# DAU_Kupplung_3phasig_V1_13.net
KiCad netlist of a schematic drawn in EAGLE
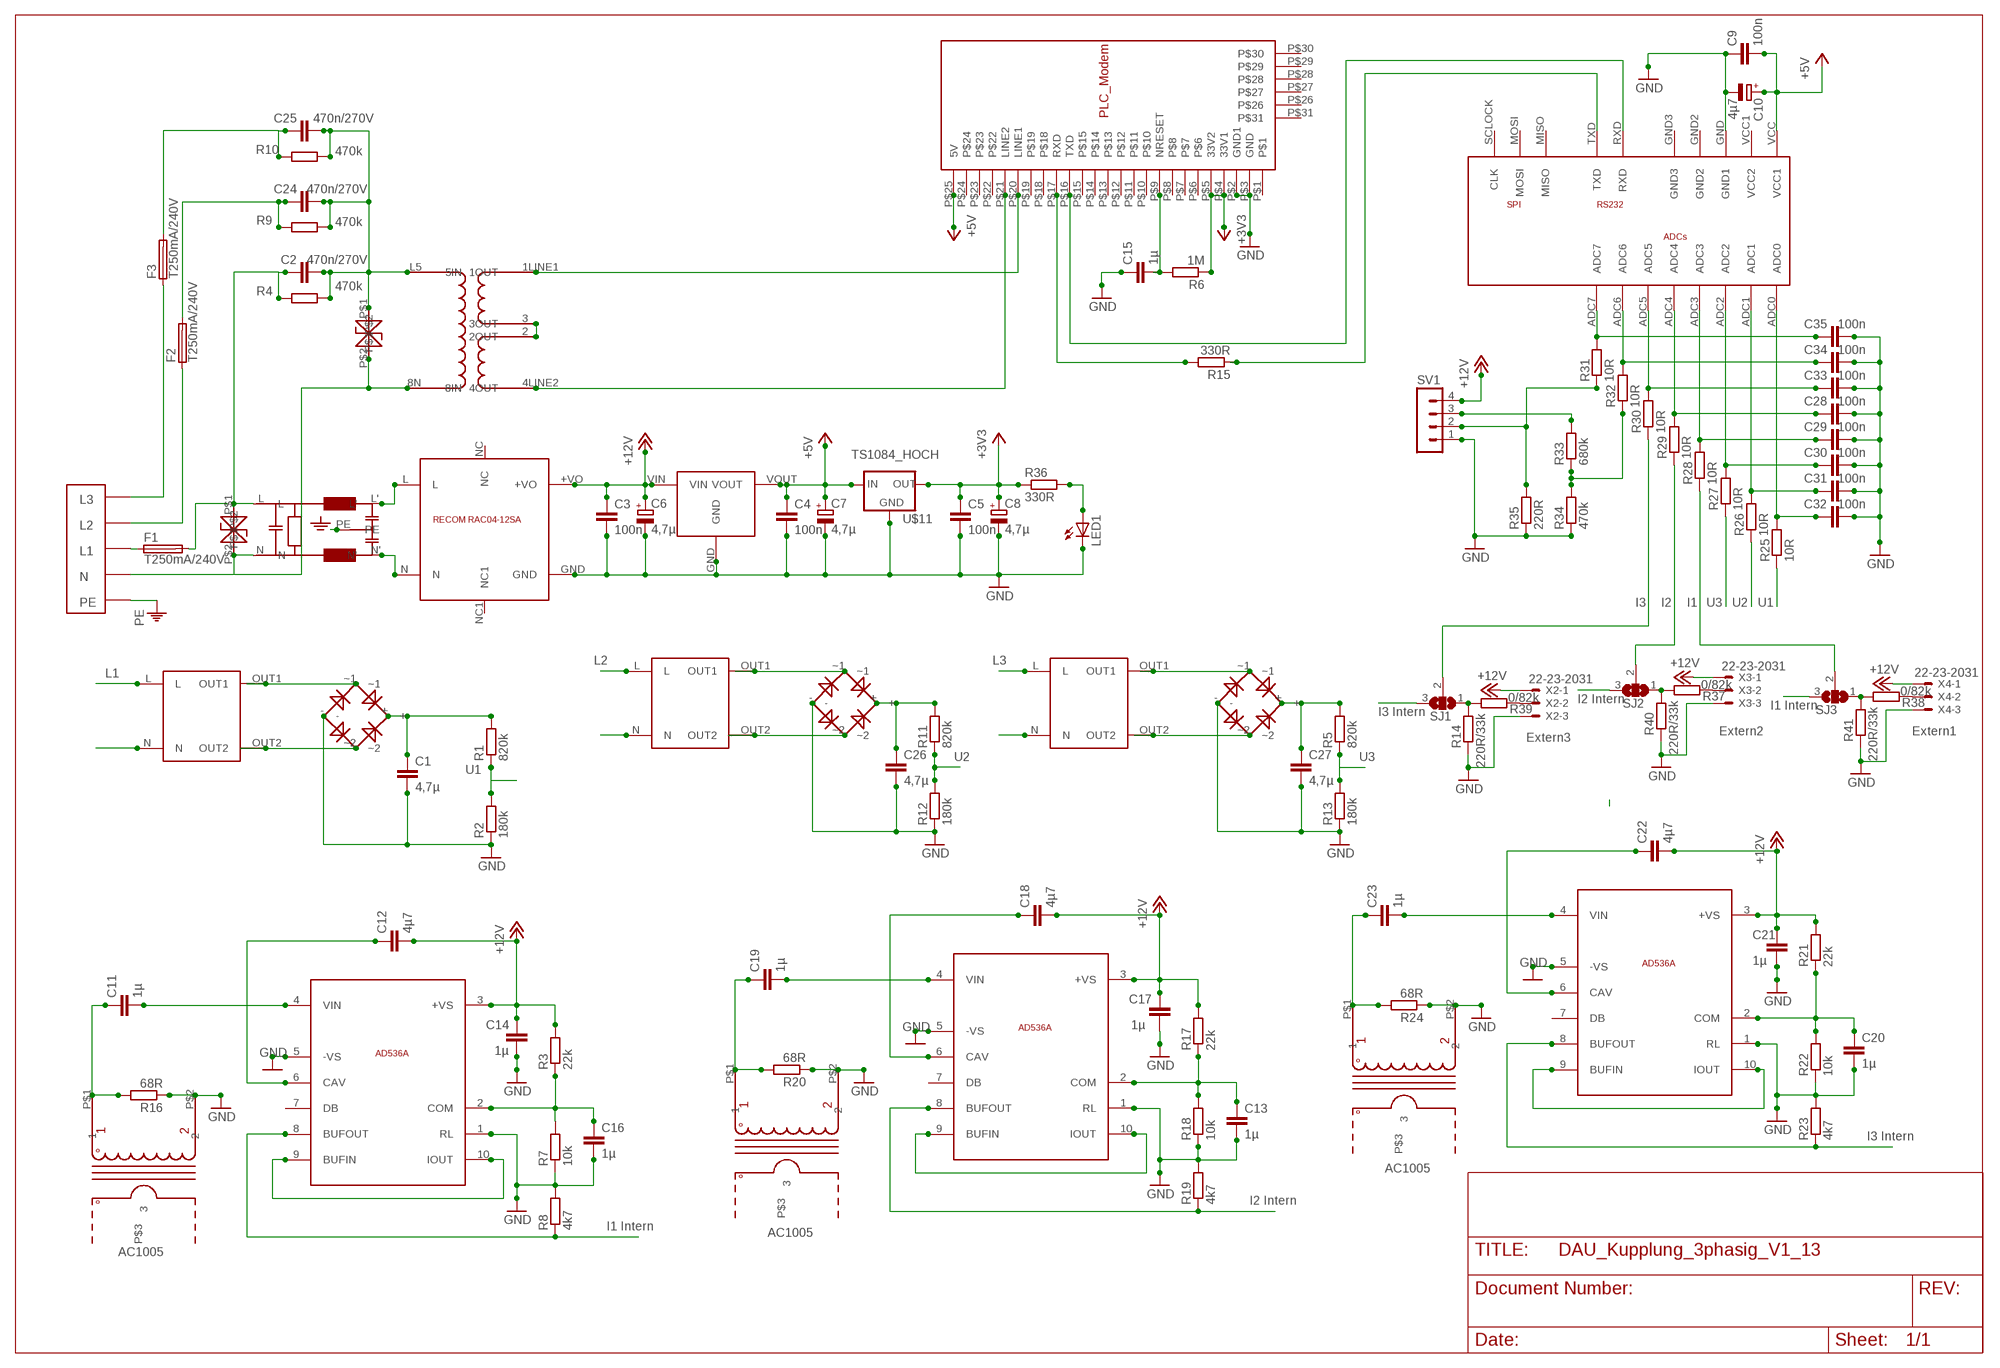
[diagram p0: schematic, sheet 1]

(export (version "E")
  (design (tool "Eeschema 10.0.6"))
  (components
    (comp (ref "AC1002_1")
      (value "AC1010")
      (footprint "eagle-import:AC1010")
      (libsource (lib "eagle-import") (part "AC1010"))
    )
    (comp (ref "C1")
      (value "4,7µ")
      (footprint "eagle-import:C1206")
      (libsource (lib "eagle-import") (part "C-EUC1206"))
    )
    (comp (ref "C2")
      (value "470n/270V")
      (footprint "eagle-import:C225-087X268")
      (libsource (lib "eagle-import") (part "C-EU225-087X268"))
    )
    (comp (ref "C3")
      (value "100n")
      (footprint "eagle-import:C0805K")
      (libsource (lib "eagle-import") (part "C-EUC0805K"))
    )
    (comp (ref "C4")
      (value "100n")
      (footprint "eagle-import:C0805K")
      (libsource (lib "eagle-import") (part "C-EUC0805K"))
    )
    (comp (ref "C5")
      (value "100n")
      (footprint "eagle-import:C0805K")
      (libsource (lib "eagle-import") (part "C-EUC0805K"))
    )
    (comp (ref "C6")
      (value "4,7µ")
      (footprint "eagle-import:E2,5-6")
      (libsource (lib "eagle-import") (part "resistor_CPOL-EUE2.5-6"))
    )
    (comp (ref "C7")
      (value "4,7µ")
      (footprint "eagle-import:E2,5-6")
      (libsource (lib "eagle-import") (part "resistor_CPOL-EUE2.5-6"))
    )
    (comp (ref "C8")
      (value "4,7µ")
      (footprint "eagle-import:E2,5-6")
      (libsource (lib "eagle-import") (part "resistor_CPOL-EUE2.5-6"))
    )
    (comp (ref "C9")
      (value "100n")
      (footprint "eagle-import:C0805K")
      (libsource (lib "eagle-import") (part "C-EUC0805K"))
    )
    (comp (ref "C10")
      (value "4µ7")
      (footprint "eagle-import:E2,5-6E")
      (libsource (lib "eagle-import") (part "CPOL-EUE2,5-6E"))
    )
    (comp (ref "C11")
      (value "1µ")
      (footprint "eagle-import:C0805K")
      (libsource (lib "eagle-import") (part "C-EUC0805K"))
    )
    (comp (ref "C12")
      (value "4µ7")
      (footprint "eagle-import:C0805K")
      (libsource (lib "eagle-import") (part "C-EUC0805K"))
    )
    (comp (ref "C13")
      (value "1µ")
      (footprint "eagle-import:C0805K")
      (libsource (lib "eagle-import") (part "C-EUC0805K"))
    )
    (comp (ref "C14")
      (value "1µ")
      (footprint "eagle-import:C0805K")
      (libsource (lib "eagle-import") (part "C-EUC0805K"))
    )
    (comp (ref "C15")
      (value "1µ")
      (footprint "eagle-import:C0805K")
      (libsource (lib "eagle-import") (part "C-EUC0805K"))
    )
    (comp (ref "C16")
      (value "1µ")
      (footprint "eagle-import:C0805K")
      (libsource (lib "eagle-import") (part "C-EUC0805K"))
    )
    (comp (ref "C17")
      (value "1µ")
      (footprint "eagle-import:C0805K")
      (libsource (lib "eagle-import") (part "C-EUC0805K"))
    )
    (comp (ref "C18")
      (value "4µ7")
      (footprint "eagle-import:C0805K")
      (libsource (lib "eagle-import") (part "C-EUC0805K"))
    )
    (comp (ref "C19")
      (value "1µ")
      (footprint "eagle-import:C0805K")
      (libsource (lib "eagle-import") (part "C-EUC0805K"))
    )
    (comp (ref "C20")
      (value "1µ")
      (footprint "eagle-import:C0805K")
      (libsource (lib "eagle-import") (part "C-EUC0805K"))
    )
    (comp (ref "C21")
      (value "1µ")
      (footprint "eagle-import:C0805K")
      (libsource (lib "eagle-import") (part "C-EUC0805K"))
    )
    (comp (ref "C22")
      (value "4µ7")
      (footprint "eagle-import:C0805K")
      (libsource (lib "eagle-import") (part "C-EUC0805K"))
    )
    (comp (ref "C23")
      (value "1µ")
      (footprint "eagle-import:C0805K")
      (libsource (lib "eagle-import") (part "C-EUC0805K"))
    )
    (comp (ref "C24")
      (value "470n/270V")
      (footprint "eagle-import:C225-087X268")
      (libsource (lib "eagle-import") (part "C-EU225-087X268"))
    )
    (comp (ref "C25")
      (value "470n/270V")
      (footprint "eagle-import:C225-087X268")
      (libsource (lib "eagle-import") (part "C-EU225-087X268"))
    )
    (comp (ref "C26")
      (value "4,7µ")
      (footprint "eagle-import:C1206")
      (libsource (lib "eagle-import") (part "C-EUC1206"))
    )
    (comp (ref "C27")
      (value "4,7µ")
      (footprint "eagle-import:C1206")
      (libsource (lib "eagle-import") (part "C-EUC1206"))
    )
    (comp (ref "C28")
      (value "100n")
      (footprint "eagle-import:C0805K")
      (libsource (lib "eagle-import") (part "C-EUC0805K"))
    )
    (comp (ref "C29")
      (value "100n")
      (footprint "eagle-import:C0805K")
      (libsource (lib "eagle-import") (part "C-EUC0805K"))
    )
    (comp (ref "C30")
      (value "100n")
      (footprint "eagle-import:C0805K")
      (libsource (lib "eagle-import") (part "C-EUC0805K"))
    )
    (comp (ref "C31")
      (value "100n")
      (footprint "eagle-import:C0805K")
      (libsource (lib "eagle-import") (part "C-EUC0805K"))
    )
    (comp (ref "C32")
      (value "100n")
      (footprint "eagle-import:C0805K")
      (libsource (lib "eagle-import") (part "C-EUC0805K"))
    )
    (comp (ref "C33")
      (value "100n")
      (footprint "eagle-import:C0805K")
      (libsource (lib "eagle-import") (part "C-EUC0805K"))
    )
    (comp (ref "C34")
      (value "100n")
      (footprint "eagle-import:C0805K")
      (libsource (lib "eagle-import") (part "C-EUC0805K"))
    )
    (comp (ref "C35")
      (value "100n")
      (footprint "eagle-import:C0805K")
      (libsource (lib "eagle-import") (part "C-EUC0805K"))
    )
    (comp (ref "F1")
      (value "T250mA/240V")
      (footprint "eagle-import:TR5")
      (libsource (lib "eagle-import") (part "TR5"))
    )
    (comp (ref "F2")
      (value "T250mA/240V")
      (footprint "eagle-import:TR5")
      (fields (field (name "OC_FARNELL") "unknown") (field (name "OC_NEWARK") "unknown"))
      (libsource (lib "eagle-import") (part "TR5"))
    )
    (comp (ref "F3")
      (value "T250mA/240V")
      (footprint "eagle-import:TR5")
      (fields (field (name "OC_FARNELL") "unknown") (field (name "OC_NEWARK") "unknown"))
      (libsource (lib "eagle-import") (part "TR5"))
    )
    (comp (ref "LED1")
      (value "LEDSQR2X5")
      (footprint "eagle-import:LED2X5")
      (libsource (lib "eagle-import") (part "LEDSQR2X5"))
    )
    (comp (ref "P6KE300CA")
      (value "P6KE300CA")
      (footprint "eagle-import:TSV")
      (libsource (lib "eagle-import") (part "TSV"))
    )
    (comp (ref "R1")
      (value "820k")
      (footprint "eagle-import:R0805")
      (libsource (lib "eagle-import") (part "R-EU_R0805"))
    )
    (comp (ref "R2")
      (value "180k")
      (footprint "eagle-import:R0805")
      (libsource (lib "eagle-import") (part "R-EU_R0805"))
    )
    (comp (ref "R3")
      (value "22k")
      (footprint "eagle-import:R0805")
      (libsource (lib "eagle-import") (part "R-EU_R0805"))
    )
    (comp (ref "R4")
      (value "470k")
      (footprint "eagle-import:0204_7")
      (libsource (lib "eagle-import") (part "R-EU_0204/7"))
    )
    (comp (ref "R5")
      (value "820k")
      (footprint "eagle-import:R0805")
      (libsource (lib "eagle-import") (part "R-EU_R0805"))
    )
    (comp (ref "R6")
      (value "1M")
      (footprint "eagle-import:R0805")
      (libsource (lib "eagle-import") (part "R-EU_R0805"))
    )
    (comp (ref "R7")
      (value "10k")
      (footprint "eagle-import:R0805")
      (libsource (lib "eagle-import") (part "R-EU_R0805"))
    )
    (comp (ref "R8")
      (value "4k7")
      (footprint "eagle-import:R0805")
      (libsource (lib "eagle-import") (part "R-EU_R0805"))
    )
    (comp (ref "R9")
      (value "470k")
      (footprint "eagle-import:0204_7")
      (libsource (lib "eagle-import") (part "R-EU_0204/7"))
    )
    (comp (ref "R10")
      (value "470k")
      (footprint "eagle-import:0204_7")
      (libsource (lib "eagle-import") (part "R-EU_0204/7"))
    )
    (comp (ref "R11")
      (value "820k")
      (footprint "eagle-import:R0805")
      (libsource (lib "eagle-import") (part "R-EU_R0805"))
    )
    (comp (ref "R12")
      (value "180k")
      (footprint "eagle-import:R0805")
      (libsource (lib "eagle-import") (part "R-EU_R0805"))
    )
    (comp (ref "R13")
      (value "180k")
      (footprint "eagle-import:R0805")
      (libsource (lib "eagle-import") (part "R-EU_R0805"))
    )
    (comp (ref "R14")
      (value "220R/33k")
      (footprint "eagle-import:R0805")
      (libsource (lib "eagle-import") (part "R-EU_R0805"))
    )
    (comp (ref "R15")
      (value "330R")
      (footprint "eagle-import:R0805")
      (libsource (lib "eagle-import") (part "R-EU_R0805"))
    )
    (comp (ref "R16")
      (value "68R")
      (footprint "eagle-import:0204_7")
      (libsource (lib "eagle-import") (part "R-EU_0204/7"))
    )
    (comp (ref "R17")
      (value "22k")
      (footprint "eagle-import:R0805")
      (libsource (lib "eagle-import") (part "R-EU_R0805"))
    )
    (comp (ref "R18")
      (value "10k")
      (footprint "eagle-import:R0805")
      (libsource (lib "eagle-import") (part "R-EU_R0805"))
    )
    (comp (ref "R19")
      (value "4k7")
      (footprint "eagle-import:R0805")
      (libsource (lib "eagle-import") (part "R-EU_R0805"))
    )
    (comp (ref "R20")
      (value "68R")
      (footprint "eagle-import:0204_7")
      (libsource (lib "eagle-import") (part "R-EU_0204/7"))
    )
    (comp (ref "R21")
      (value "22k")
      (footprint "eagle-import:R0805")
      (libsource (lib "eagle-import") (part "R-EU_R0805"))
    )
    (comp (ref "R22")
      (value "10k")
      (footprint "eagle-import:R0805")
      (libsource (lib "eagle-import") (part "R-EU_R0805"))
    )
    (comp (ref "R23")
      (value "4k7")
      (footprint "eagle-import:R0805")
      (libsource (lib "eagle-import") (part "R-EU_R0805"))
    )
    (comp (ref "R24")
      (value "68R")
      (footprint "eagle-import:0204_7")
      (libsource (lib "eagle-import") (part "R-EU_0204/7"))
    )
    (comp (ref "R25")
      (value "10R")
      (footprint "eagle-import:R0805")
      (libsource (lib "eagle-import") (part "R-EU_R0805"))
    )
    (comp (ref "R26")
      (value "10R")
      (footprint "eagle-import:R0805")
      (libsource (lib "eagle-import") (part "R-EU_R0805"))
    )
    (comp (ref "R27")
      (value "10R")
      (footprint "eagle-import:R0805")
      (libsource (lib "eagle-import") (part "R-EU_R0805"))
    )
    (comp (ref "R28")
      (value "10R")
      (footprint "eagle-import:R0805")
      (libsource (lib "eagle-import") (part "R-EU_R0805"))
    )
    (comp (ref "R29")
      (value "10R")
      (footprint "eagle-import:R0805")
      (libsource (lib "eagle-import") (part "R-EU_R0805"))
    )
    (comp (ref "R30")
      (value "10R")
      (footprint "eagle-import:R0805")
      (libsource (lib "eagle-import") (part "R-EU_R0805"))
    )
    (comp (ref "R31")
      (value "10R")
      (footprint "eagle-import:R0805")
      (libsource (lib "eagle-import") (part "R-EU_R0805"))
    )
    (comp (ref "R32")
      (value "10R")
      (footprint "eagle-import:R0805")
      (libsource (lib "eagle-import") (part "R-EU_R0805"))
    )
    (comp (ref "R33")
      (value "680k")
      (footprint "eagle-import:R0805")
      (libsource (lib "eagle-import") (part "R-EU_R0805"))
    )
    (comp (ref "R34")
      (value "470k")
      (footprint "eagle-import:R0805")
      (libsource (lib "eagle-import") (part "R-EU_R0805"))
    )
    (comp (ref "R35")
      (value "220R")
      (footprint "eagle-import:R0805")
      (libsource (lib "eagle-import") (part "R-EU_R0805"))
    )
    (comp (ref "R36")
      (value "330R")
      (footprint "eagle-import:R0805")
      (libsource (lib "eagle-import") (part "R-EU_R0805"))
    )
    (comp (ref "R37")
      (value "0/82k")
      (footprint "eagle-import:R0805")
      (libsource (lib "eagle-import") (part "R-EU_R0805"))
    )
    (comp (ref "R38")
      (value "0/82k")
      (footprint "eagle-import:R0805")
      (libsource (lib "eagle-import") (part "R-EU_R0805"))
    )
    (comp (ref "R39")
      (value "0/82k")
      (footprint "eagle-import:R0805")
      (libsource (lib "eagle-import") (part "R-EU_R0805"))
    )
    (comp (ref "R40")
      (value "220R/33k")
      (footprint "eagle-import:R0805")
      (libsource (lib "eagle-import") (part "R-EU_R0805"))
    )
    (comp (ref "R41")
      (value "220R/33k")
      (footprint "eagle-import:R0805")
      (libsource (lib "eagle-import") (part "R-EU_R0805"))
    )
    (comp (ref "SJ1")
      (value "SJ2WW")
      (footprint "eagle-import:SJ_2W")
      (libsource (lib "eagle-import") (part "SJ2WW"))
    )
    (comp (ref "SJ2")
      (value "SJ2WW")
      (footprint "eagle-import:SJ_2W")
      (libsource (lib "eagle-import") (part "SJ2WW"))
    )
    (comp (ref "SJ3")
      (value "SJ2WW")
      (footprint "eagle-import:SJ_2W")
      (libsource (lib "eagle-import") (part "SJ2WW"))
    )
    (comp (ref "SV1")
      (value "MA04-1")
      (footprint "eagle-import:MA04-1")
      (libsource (lib "eagle-import") (part "MA04-1"))
    )
    (comp (ref "TSV2")
      (value "TSV")
      (footprint "eagle-import:TSV")
      (libsource (lib "eagle-import") (part "TSV"))
    )
    (comp (ref "U$1")
      (value "RECOM_RAC04_12SA")
      (footprint "eagle-import:RAC04_12SA")
      (libsource (lib "eagle-import") (part "RECOM_RAC04_12SA"))
    )
    (comp (ref "U$2")
      (value "SICHERHEITSTRAFO")
      (footprint "eagle-import:TRAFO_0,35VA")
      (libsource (lib "eagle-import") (part "SICHERHEITSTRAFO"))
    )
    (comp (ref "U$3")
      (value "ADUC831_MINIMUM")
      (footprint "eagle-import:ADUC_MINIMUM")
      (libsource (lib "eagle-import") (part "ADUC831_MINIMUM"))
    )
    (comp (ref "U$4")
      (value "MODEMSTECKER")
      (footprint "eagle-import:MODEM_FUSS")
      (libsource (lib "eagle-import") (part "MODEMSTECKER"))
    )
    (comp (ref "U$5")
      (value "PLC_UEBERTRAGER_V2")
      (footprint "eagle-import:PLC-UEBERTRAGER_V2")
      (libsource (lib "eagle-import") (part "PLC_UEBERTRAGER_V2"))
    )
    (comp (ref "U$7")
      (value "AC1010")
      (footprint "eagle-import:AC1010")
      (libsource (lib "eagle-import") (part "AC1010"))
    )
    (comp (ref "U$8")
      (value "RECTIFIER")
      (footprint "eagle-import:RECTIFIER")
      (libsource (lib "eagle-import") (part "RECTIFIER"))
    )
    (comp (ref "U$10")
      (value "RECOM_785_05")
      (footprint "eagle-import:RECOM785X")
      (libsource (lib "eagle-import") (part "RECOM_785_05"))
    )
    (comp (ref "U$11")
      (value "TS1084_HOCH")
      (footprint "eagle-import:TS1084_HOCH")
      (libsource (lib "eagle-import") (part "TS1084_HOCH"))
    )
    (comp (ref "U$12")
      (value "AD536")
      (footprint "eagle-import:TO100_10PIN")
      (libsource (lib "eagle-import") (part "AD536"))
    )
    (comp (ref "U$13")
      (value "AD536")
      (footprint "eagle-import:TO100_10PIN")
      (libsource (lib "eagle-import") (part "AD536"))
    )
    (comp (ref "U$14")
      (value "AC1010")
      (footprint "eagle-import:AC1010")
      (libsource (lib "eagle-import") (part "AC1010"))
    )
    (comp (ref "U$15")
      (value "AD536")
      (footprint "eagle-import:TO100_10PIN")
      (libsource (lib "eagle-import") (part "AD536"))
    )
    (comp (ref "U$16")
      (value "SICHERHEITSTRAFO")
      (footprint "eagle-import:TRAFO_0,35VA")
      (libsource (lib "eagle-import") (part "SICHERHEITSTRAFO"))
    )
    (comp (ref "U$17")
      (value "RECTIFIER")
      (footprint "eagle-import:RECTIFIER")
      (libsource (lib "eagle-import") (part "RECTIFIER"))
    )
    (comp (ref "U$18")
      (value "SICHERHEITSTRAFO")
      (footprint "eagle-import:TRAFO_0,35VA")
      (libsource (lib "eagle-import") (part "SICHERHEITSTRAFO"))
    )
    (comp (ref "U$19")
      (value "RECTIFIER")
      (footprint "eagle-import:RECTIFIER")
      (libsource (lib "eagle-import") (part "RECTIFIER"))
    )
    (comp (ref "U$20")
      (value "NETZFILTER_05_A")
      (footprint "eagle-import:NETZFILTER")
      (libsource (lib "eagle-import") (part "NETZFILTER_05_A"))
    )
    (comp (ref "X1")
      (value "CONNECTO_5_POL")
      (footprint "eagle-import:CONNECTOR_5_POL")
      (libsource (lib "eagle-import") (part "CONNECTO_5_POL"))
    )
    (comp (ref "X2")
      (value "22-23-2031")
      (footprint "eagle-import:22-23-2031")
      (fields (field (name "MF") "MOLEX"))
      (libsource (lib "eagle-import") (part "22-23-2031"))
    )
    (comp (ref "X3")
      (value "22-23-2031")
      (footprint "eagle-import:22-23-2031")
      (fields (field (name "MF") "MOLEX"))
      (libsource (lib "eagle-import") (part "22-23-2031"))
    )
    (comp (ref "X4")
      (value "22-23-2031")
      (footprint "eagle-import:22-23-2031")
      (fields (field (name "MF") "MOLEX"))
      (libsource (lib "eagle-import") (part "22-23-2031"))
    )
  )
  (nets
    (net (code "1") (name "+3V3") (class "Default")
      (node (ref "C5") (pin "1") (pinfunction "1_1") (pintype "passive"))
      (node (ref "C8") (pin "+") (pinfunction "+_+") (pintype "passive"))
      (node (ref "R36") (pin "1") (pinfunction "1_1") (pintype "passive"))
      (node (ref "R6") (pin "1") (pinfunction "1_1") (pintype "passive"))
      (node (ref "U$11") (pin "OUT") (pinfunction "OUT_OUT") (pintype "passive"))
      (node (ref "U$4") (pin "P$4") (pinfunction "33V1_P$4") (pintype "bidirectional"))
      (node (ref "U$4") (pin "P$5") (pinfunction "33V2_P$5") (pintype "bidirectional"))
    )
    (net (code "2") (name "+5V") (class "Default")
      (node (ref "C10") (pin "+") (pinfunction "+_+") (pintype "passive"))
      (node (ref "C4") (pin "1") (pinfunction "1_1") (pintype "passive"))
      (node (ref "C7") (pin "+") (pinfunction "+_+") (pintype "passive"))
      (node (ref "C9") (pin "2") (pinfunction "2_2") (pintype "passive"))
      (node (ref "U$10") (pin "VOUT") (pinfunction "VOUT_VOUT") (pintype "bidirectional"))
      (node (ref "U$11") (pin "IN") (pinfunction "IN_IN") (pintype "input"))
      (node (ref "U$3") (pin "VCC") (pinfunction "VCC1_VCC") (pintype "bidirectional"))
      (node (ref "U$4") (pin "P$25") (pinfunction "5V_P$25") (pintype "bidirectional"))
    )
    (net (code "3") (name "+12V") (class "Default")
      (node (ref "C12") (pin "2") (pinfunction "2_2") (pintype "passive"))
      (node (ref "C14") (pin "2") (pinfunction "2_2") (pintype "passive"))
      (node (ref "C17") (pin "2") (pinfunction "2_2") (pintype "passive"))
      (node (ref "C18") (pin "2") (pinfunction "2_2") (pintype "passive"))
      (node (ref "C21") (pin "1") (pinfunction "1_1") (pintype "passive"))
      (node (ref "C22") (pin "2") (pinfunction "2_2") (pintype "passive"))
      (node (ref "C3") (pin "1") (pinfunction "1_1") (pintype "passive"))
      (node (ref "C6") (pin "+") (pinfunction "+_+") (pintype "passive"))
      (node (ref "R17") (pin "2") (pinfunction "2_2") (pintype "passive"))
      (node (ref "R21") (pin "2") (pinfunction "2_2") (pintype "passive"))
      (node (ref "R3") (pin "2") (pinfunction "2_2") (pintype "passive"))
      (node (ref "SV1") (pin "4") (pinfunction "4_4") (pintype "passive"))
      (node (ref "U$1") (pin "+VO") (pinfunction "+VO_+VO") (pintype "bidirectional"))
      (node (ref "U$10") (pin "VIN") (pinfunction "VIN_VIN") (pintype "bidirectional"))
      (node (ref "U$12") (pin "3") (pinfunction "+VS_3") (pintype "bidirectional"))
      (node (ref "U$13") (pin "3") (pinfunction "+VS_3") (pintype "bidirectional"))
      (node (ref "U$15") (pin "3") (pinfunction "+VS_3") (pintype "bidirectional"))
      (node (ref "X2") (pin "1") (pinfunction "S_1") (pintype "passive"))
      (node (ref "X3") (pin "1") (pinfunction "S_1") (pintype "passive"))
      (node (ref "X4") (pin "1") (pinfunction "S_1") (pintype "passive"))
    )
    (net (code "4") (name "/I1INTERN") (class "Default")
      (node (ref "R8") (pin "1") (pinfunction "1_1") (pintype "passive"))
      (node (ref "SJ3") (pin "3") (pinfunction "3_3") (pintype "passive"))
      (node (ref "U$13") (pin "8") (pinfunction "BUFOUT_8") (pintype "bidirectional"))
    )
    (net (code "5") (name "/I2INTERN") (class "Default")
      (node (ref "R19") (pin "1") (pinfunction "1_1") (pintype "passive"))
      (node (ref "SJ2") (pin "3") (pinfunction "3_3") (pintype "passive"))
      (node (ref "U$12") (pin "8") (pinfunction "BUFOUT_8") (pintype "bidirectional"))
    )
    (net (code "6") (name "/I3INTERN") (class "Default")
      (node (ref "R23") (pin "1") (pinfunction "1_1") (pintype "passive"))
      (node (ref "SJ1") (pin "3") (pinfunction "3_3") (pintype "passive"))
      (node (ref "U$15") (pin "8") (pinfunction "BUFOUT_8") (pintype "bidirectional"))
    )
    (net (code "7") (name "/L1") (class "Default")
      (node (ref "C2") (pin "1") (pinfunction "1_1") (pintype "passive"))
      (node (ref "F1") (pin "2") (pinfunction "2_2") (pintype "passive"))
      (node (ref "P6KE300CA") (pin "P$1") (pinfunction "P$1_P$1") (pintype "bidirectional"))
      (node (ref "R4") (pin "2") (pinfunction "2_2") (pintype "passive"))
      (node (ref "U$2") (pin "L") (pinfunction "L_L") (pintype "bidirectional"))
      (node (ref "U$20") (pin "L") (pinfunction "L_L") (pintype "bidirectional"))
    )
    (net (code "8") (name "/L2") (class "Default")
      (node (ref "C24") (pin "1") (pinfunction "1_1") (pintype "passive"))
      (node (ref "F2") (pin "2") (pinfunction "2_2") (pintype "passive"))
      (node (ref "R9") (pin "2") (pinfunction "2_2") (pintype "passive"))
      (node (ref "U$16") (pin "L") (pinfunction "L_L") (pintype "bidirectional"))
    )
    (net (code "9") (name "/L3") (class "Default")
      (node (ref "C25") (pin "1") (pinfunction "1_1") (pintype "passive"))
      (node (ref "F3") (pin "2") (pinfunction "2_2") (pintype "passive"))
      (node (ref "R10") (pin "2") (pinfunction "2_2") (pintype "passive"))
      (node (ref "U$18") (pin "L") (pinfunction "L_L") (pintype "bidirectional"))
    )
    (net (code "10") (name "/N") (class "Default")
      (node (ref "P6KE300CA") (pin "P$2") (pinfunction "P$2_P$2") (pintype "bidirectional"))
      (node (ref "TSV2") (pin "P$2") (pinfunction "P$2_P$2") (pintype "bidirectional"))
      (node (ref "U$16") (pin "N") (pinfunction "N_N") (pintype "bidirectional"))
      (node (ref "U$18") (pin "N") (pinfunction "N_N") (pintype "bidirectional"))
      (node (ref "U$2") (pin "N") (pinfunction "N_N") (pintype "bidirectional"))
      (node (ref "U$20") (pin "N") (pinfunction "N_N") (pintype "bidirectional"))
      (node (ref "U$5") (pin "8N") (pinfunction "8IN_8N") (pintype "input"))
      (node (ref "X1") (pin "P$4") (pinfunction "P$4_P$4") (pintype "bidirectional"))
    )
    (net (code "11") (name "/U1") (class "Default")
      (node (ref "R1") (pin "1") (pinfunction "1_1") (pintype "passive"))
      (node (ref "R2") (pin "2") (pinfunction "2_2") (pintype "passive"))
      (node (ref "R25") (pin "1") (pinfunction "1_1") (pintype "passive"))
    )
    (net (code "12") (name "/U2") (class "Default")
      (node (ref "R11") (pin "1") (pinfunction "1_1") (pintype "passive"))
      (node (ref "R12") (pin "2") (pinfunction "2_2") (pintype "passive"))
      (node (ref "R26") (pin "1") (pinfunction "1_1") (pintype "passive"))
    )
    (net (code "13") (name "/U3") (class "Default")
      (node (ref "R13") (pin "2") (pinfunction "2_2") (pintype "passive"))
      (node (ref "R27") (pin "1") (pinfunction "1_1") (pintype "passive"))
      (node (ref "R5") (pin "1") (pinfunction "1_1") (pintype "passive"))
    )
    (net (code "14") (name "GND") (class "Default")
      (node (ref "AC1002_1") (pin "P$2") (pinfunction "2_P$2") (pintype "output"))
      (node (ref "C1") (pin "2") (pinfunction "2_2") (pintype "passive"))
      (node (ref "C10") (pin "-") (pinfunction "-_-") (pintype "passive"))
      (node (ref "C13") (pin "2") (pinfunction "2_2") (pintype "passive"))
      (node (ref "C14") (pin "1") (pinfunction "1_1") (pintype "passive"))
      (node (ref "C15") (pin "1") (pinfunction "1_1") (pintype "passive"))
      (node (ref "C16") (pin "2") (pinfunction "2_2") (pintype "passive"))
      (node (ref "C17") (pin "1") (pinfunction "1_1") (pintype "passive"))
      (node (ref "C20") (pin "2") (pinfunction "2_2") (pintype "passive"))
      (node (ref "C21") (pin "2") (pinfunction "2_2") (pintype "passive"))
      (node (ref "C26") (pin "2") (pinfunction "2_2") (pintype "passive"))
      (node (ref "C27") (pin "2") (pinfunction "2_2") (pintype "passive"))
      (node (ref "C28") (pin "2") (pinfunction "2_2") (pintype "passive"))
      (node (ref "C29") (pin "2") (pinfunction "2_2") (pintype "passive"))
      (node (ref "C3") (pin "2") (pinfunction "2_2") (pintype "passive"))
      (node (ref "C30") (pin "2") (pinfunction "2_2") (pintype "passive"))
      (node (ref "C31") (pin "2") (pinfunction "2_2") (pintype "passive"))
      (node (ref "C32") (pin "2") (pinfunction "2_2") (pintype "passive"))
      (node (ref "C33") (pin "2") (pinfunction "2_2") (pintype "passive"))
      (node (ref "C34") (pin "2") (pinfunction "2_2") (pintype "passive"))
      (node (ref "C35") (pin "2") (pinfunction "2_2") (pintype "passive"))
      (node (ref "C4") (pin "2") (pinfunction "2_2") (pintype "passive"))
      (node (ref "C5") (pin "2") (pinfunction "2_2") (pintype "passive"))
      (node (ref "C6") (pin "-") (pinfunction "-_-") (pintype "passive"))
      (node (ref "C7") (pin "-") (pinfunction "-_-") (pintype "passive"))
      (node (ref "C8") (pin "-") (pinfunction "-_-") (pintype "passive"))
      (node (ref "C9") (pin "1") (pinfunction "1_1") (pintype "passive"))
      (node (ref "LED1") (pin "K") (pinfunction "C_K") (pintype "passive"))
      (node (ref "R12") (pin "1") (pinfunction "1_1") (pintype "passive"))
      (node (ref "R13") (pin "1") (pinfunction "1_1") (pintype "passive"))
      (node (ref "R14") (pin "1") (pinfunction "1_1") (pintype "passive"))
      (node (ref "R16") (pin "1") (pinfunction "1_1") (pintype "passive"))
      (node (ref "R18") (pin "1") (pinfunction "1_1") (pintype "passive"))
      (node (ref "R19") (pin "2") (pinfunction "2_2") (pintype "passive"))
      (node (ref "R2") (pin "1") (pinfunction "1_1") (pintype "passive"))
      (node (ref "R20") (pin "1") (pinfunction "1_1") (pintype "passive"))
      (node (ref "R22") (pin "1") (pinfunction "1_1") (pintype "passive"))
      (node (ref "R23") (pin "2") (pinfunction "2_2") (pintype "passive"))
      (node (ref "R24") (pin "1") (pinfunction "1_1") (pintype "passive"))
      (node (ref "R34") (pin "1") (pinfunction "1_1") (pintype "passive"))
      (node (ref "R35") (pin "1") (pinfunction "1_1") (pintype "passive"))
      (node (ref "R40") (pin "1") (pinfunction "1_1") (pintype "passive"))
      (node (ref "R41") (pin "1") (pinfunction "1_1") (pintype "passive"))
      (node (ref "R7") (pin "1") (pinfunction "1_1") (pintype "passive"))
      (node (ref "R8") (pin "2") (pinfunction "2_2") (pintype "passive"))
      (node (ref "SV1") (pin "1") (pinfunction "1_1") (pintype "passive"))
      (node (ref "U$1") (pin "GND") (pinfunction "GND_GND") (pintype "bidirectional"))
      (node (ref "U$10") (pin "GND") (pinfunction "GND_GND") (pintype "bidirectional"))
      (node (ref "U$11") (pin "GND") (pinfunction "GND_GND") (pintype "input"))
      (node (ref "U$12") (pin "1") (pinfunction "RL_1") (pintype "bidirectional"))
      (node (ref "U$12") (pin "5") (pinfunction "-VS_5") (pintype "bidirectional"))
      (node (ref "U$13") (pin "1") (pinfunction "RL_1") (pintype "bidirectional"))
      (node (ref "U$13") (pin "5") (pinfunction "-VS_5") (pintype "bidirectional"))
      (node (ref "U$14") (pin "P$2") (pinfunction "2_P$2") (pintype "output"))
      (node (ref "U$15") (pin "1") (pinfunction "RL_1") (pintype "bidirectional"))
      (node (ref "U$15") (pin "5") (pinfunction "-VS_5") (pintype "bidirectional"))
      (node (ref "U$17") (pin "-") (pinfunction "-_-") (pintype "bidirectional"))
      (node (ref "U$19") (pin "-") (pinfunction "-_-") (pintype "bidirectional"))
      (node (ref "U$3") (pin "GND") (pinfunction "GND1_GND") (pintype "bidirectional"))
      (node (ref "U$4") (pin "P$2") (pinfunction "GND1_P$2") (pintype "bidirectional"))
      (node (ref "U$4") (pin "P$3") (pinfunction "GND_P$3") (pintype "bidirectional"))
      (node (ref "U$7") (pin "P$2") (pinfunction "2_P$2") (pintype "output"))
      (node (ref "U$8") (pin "-") (pinfunction "-_-") (pintype "bidirectional"))
      (node (ref "X2") (pin "3") (pinfunction "S_3") (pintype "passive"))
      (node (ref "X3") (pin "3") (pinfunction "S_3") (pintype "passive"))
      (node (ref "X4") (pin "3") (pinfunction "S_3") (pintype "passive"))
    )
    (net (code "15") (name "Net-(AC1002_1-1)") (class "Default")
      (node (ref "AC1002_1") (pin "P$1") (pinfunction "1_P$1") (pintype "output"))
      (node (ref "C11") (pin "1") (pinfunction "1_1") (pintype "passive"))
      (node (ref "R16") (pin "2") (pinfunction "2_2") (pintype "passive"))
    )
    (net (code "16") (name "Net-(C1-Pad1)") (class "Default")
      (node (ref "C1") (pin "1") (pinfunction "1_1") (pintype "passive"))
      (node (ref "R1") (pin "2") (pinfunction "2_2") (pintype "passive"))
      (node (ref "U$8") (pin "+") (pinfunction "+_+") (pintype "bidirectional"))
    )
    (net (code "17") (name "Net-(C26-Pad1)") (class "Default")
      (node (ref "C26") (pin "1") (pinfunction "1_1") (pintype "passive"))
      (node (ref "R11") (pin "2") (pinfunction "2_2") (pintype "passive"))
      (node (ref "U$17") (pin "+") (pinfunction "+_+") (pintype "bidirectional"))
    )
    (net (code "18") (name "Net-(C27-Pad1)") (class "Default")
      (node (ref "C27") (pin "1") (pinfunction "1_1") (pintype "passive"))
      (node (ref "R5") (pin "2") (pinfunction "2_2") (pintype "passive"))
      (node (ref "U$19") (pin "+") (pinfunction "+_+") (pintype "bidirectional"))
    )
    (net (code "19") (name "Net-(C28-Pad1)") (class "Default")
      (node (ref "C28") (pin "1") (pinfunction "1_1") (pintype "passive"))
      (node (ref "R29") (pin "2") (pinfunction "2_2") (pintype "passive"))
      (node (ref "U$3") (pin "ADC4") (pinfunction "ADC4_ADC4") (pintype "bidirectional"))
    )
    (net (code "20") (name "Net-(C29-Pad1)") (class "Default")
      (node (ref "C29") (pin "1") (pinfunction "1_1") (pintype "passive"))
      (node (ref "R28") (pin "2") (pinfunction "2_2") (pintype "passive"))
      (node (ref "U$3") (pin "ADC3") (pinfunction "ADC3_ADC3") (pintype "bidirectional"))
    )
    (net (code "21") (name "Net-(C30-Pad1)") (class "Default")
      (node (ref "C30") (pin "1") (pinfunction "1_1") (pintype "passive"))
      (node (ref "R27") (pin "2") (pinfunction "2_2") (pintype "passive"))
      (node (ref "U$3") (pin "ADC2") (pinfunction "ADC2_ADC2") (pintype "bidirectional"))
    )
    (net (code "22") (name "Net-(C31-Pad1)") (class "Default")
      (node (ref "C31") (pin "1") (pinfunction "1_1") (pintype "passive"))
      (node (ref "R26") (pin "2") (pinfunction "2_2") (pintype "passive"))
      (node (ref "U$3") (pin "ADC1") (pinfunction "ADC1_ADC1") (pintype "bidirectional"))
    )
    (net (code "23") (name "Net-(C32-Pad1)") (class "Default")
      (node (ref "C32") (pin "1") (pinfunction "1_1") (pintype "passive"))
      (node (ref "R25") (pin "2") (pinfunction "2_2") (pintype "passive"))
      (node (ref "U$3") (pin "ADC0") (pinfunction "ADC0_ADC0") (pintype "bidirectional"))
    )
    (net (code "24") (name "Net-(C33-Pad1)") (class "Default")
      (node (ref "C33") (pin "1") (pinfunction "1_1") (pintype "passive"))
      (node (ref "R30") (pin "2") (pinfunction "2_2") (pintype "passive"))
      (node (ref "U$3") (pin "ADC5") (pinfunction "ADC5_ADC5") (pintype "bidirectional"))
    )
    (net (code "25") (name "Net-(C34-Pad1)") (class "Default")
      (node (ref "C34") (pin "1") (pinfunction "1_1") (pintype "passive"))
      (node (ref "R32") (pin "2") (pinfunction "2_2") (pintype "passive"))
      (node (ref "U$3") (pin "ADC6") (pinfunction "ADC6_ADC6") (pintype "bidirectional"))
    )
    (net (code "26") (name "Net-(C35-Pad1)") (class "Default")
      (node (ref "C35") (pin "1") (pinfunction "1_1") (pintype "passive"))
      (node (ref "R31") (pin "2") (pinfunction "2_2") (pintype "passive"))
      (node (ref "U$3") (pin "ADC7") (pinfunction "ADC7_ADC7") (pintype "bidirectional"))
    )
    (net (code "27") (name "Net-(F1-Pad1)") (class "Default")
      (node (ref "F1") (pin "1") (pinfunction "1_1") (pintype "passive"))
      (node (ref "X1") (pin "P$3") (pinfunction "P$3_P$3") (pintype "bidirectional"))
    )
    (net (code "28") (name "Net-(F2-Pad1)") (class "Default")
      (node (ref "F2") (pin "1") (pinfunction "1_1") (pintype "passive"))
      (node (ref "X1") (pin "P$2") (pinfunction "P$2_P$2") (pintype "bidirectional"))
    )
    (net (code "29") (name "Net-(F3-Pad1)") (class "Default")
      (node (ref "F3") (pin "1") (pinfunction "1_1") (pintype "passive"))
      (node (ref "X1") (pin "P$1") (pinfunction "P$1_P$1") (pintype "bidirectional"))
    )
    (net (code "30") (name "Net-(LED1-PadA)") (class "Default")
      (node (ref "LED1") (pin "A") (pinfunction "A_A") (pintype "passive"))
      (node (ref "R36") (pin "2") (pinfunction "2_2") (pintype "passive"))
    )
    (net (code "31") (name "Net-(R14-Pad2)") (class "Default")
      (node (ref "R14") (pin "2") (pinfunction "2_2") (pintype "passive"))
      (node (ref "R39") (pin "2") (pinfunction "2_2") (pintype "passive"))
      (node (ref "SJ1") (pin "1") (pinfunction "1_1") (pintype "passive"))
    )
    (net (code "32") (name "Net-(R15-Pad1)") (class "Default")
      (node (ref "R15") (pin "1") (pinfunction "1_1") (pintype "passive"))
      (node (ref "U$3") (pin "TXD") (pinfunction "TXD_TXD") (pintype "bidirectional"))
    )
    (net (code "33") (name "Net-(R28-Pad1)") (class "Default")
      (node (ref "R28") (pin "1") (pinfunction "1_1") (pintype "passive"))
      (node (ref "SJ3") (pin "2") (pinfunction "2_2") (pintype "passive"))
    )
    (net (code "34") (name "Net-(R29-Pad1)") (class "Default")
      (node (ref "R29") (pin "1") (pinfunction "1_1") (pintype "passive"))
      (node (ref "SJ2") (pin "2") (pinfunction "2_2") (pintype "passive"))
    )
    (net (code "35") (name "Net-(R30-Pad1)") (class "Default")
      (node (ref "R30") (pin "1") (pinfunction "1_1") (pintype "passive"))
      (node (ref "SJ1") (pin "2") (pinfunction "2_2") (pintype "passive"))
    )
    (net (code "36") (name "Net-(R31-Pad1)") (class "Default")
      (node (ref "R31") (pin "1") (pinfunction "1_1") (pintype "passive"))
      (node (ref "R35") (pin "2") (pinfunction "2_2") (pintype "passive"))
      (node (ref "SV1") (pin "2") (pinfunction "2_2") (pintype "passive"))
    )
    (net (code "37") (name "Net-(R32-Pad1)") (class "Default")
      (node (ref "R32") (pin "1") (pinfunction "1_1") (pintype "passive"))
      (node (ref "R33") (pin "1") (pinfunction "1_1") (pintype "passive"))
      (node (ref "R34") (pin "2") (pinfunction "2_2") (pintype "passive"))
    )
    (net (code "38") (name "Net-(R33-Pad2)") (class "Default")
      (node (ref "R33") (pin "2") (pinfunction "2_2") (pintype "passive"))
      (node (ref "SV1") (pin "3") (pinfunction "3_3") (pintype "passive"))
    )
    (net (code "39") (name "Net-(R37-Pad2)") (class "Default")
      (node (ref "R37") (pin "2") (pinfunction "2_2") (pintype "passive"))
      (node (ref "R40") (pin "2") (pinfunction "2_2") (pintype "passive"))
      (node (ref "SJ2") (pin "1") (pinfunction "1_1") (pintype "passive"))
    )
    (net (code "40") (name "Net-(R38-Pad2)") (class "Default")
      (node (ref "R38") (pin "2") (pinfunction "2_2") (pintype "passive"))
      (node (ref "R41") (pin "2") (pinfunction "2_2") (pintype "passive"))
      (node (ref "SJ3") (pin "1") (pinfunction "1_1") (pintype "passive"))
    )
    (net (code "41") (name "Net-(U$1-PadL)") (class "Default")
      (node (ref "U$1") (pin "L") (pinfunction "L_L") (pintype "bidirectional"))
      (node (ref "U$20") (pin "L'") (pinfunction "L'_L'") (pintype "bidirectional"))
    )
    (net (code "42") (name "Net-(U$1-PadN)") (class "Default")
      (node (ref "U$1") (pin "N") (pinfunction "N_N") (pintype "bidirectional"))
      (node (ref "U$20") (pin "N'") (pinfunction "N'_N'") (pintype "bidirectional"))
    )
    (net (code "43") (name "Net-(U$4-LINE1)") (class "Default")
      (node (ref "U$4") (pin "P$20") (pinfunction "LINE1_P$20") (pintype "bidirectional"))
      (node (ref "U$5") (pin "1LINE1") (pinfunction "1OUT_1LINE1") (pintype "output"))
    )
    (net (code "44") (name "Net-(U$4-LINE2)") (class "Default")
      (node (ref "U$4") (pin "P$21") (pinfunction "LINE2_P$21") (pintype "bidirectional"))
      (node (ref "U$5") (pin "4LINE2") (pinfunction "4OUT_4LINE2") (pintype "output"))
    )
    (net (code "45") (name "Net-(U$4-NRESET)") (class "Default")
      (node (ref "C15") (pin "2") (pinfunction "2_2") (pintype "passive"))
      (node (ref "R6") (pin "2") (pinfunction "2_2") (pintype "passive"))
      (node (ref "U$4") (pin "P$9") (pinfunction "NRESET_P$9") (pintype "bidirectional"))
    )
    (net (code "46") (name "Net-(U$4-RXD)") (class "Default")
      (node (ref "R15") (pin "2") (pinfunction "2_2") (pintype "passive"))
      (node (ref "U$4") (pin "P$17") (pinfunction "RXD_P$17") (pintype "bidirectional"))
    )
    (net (code "47") (name "Net-(U$4-TXD)") (class "Default")
      (node (ref "U$3") (pin "RXD") (pinfunction "RXD_RXD") (pintype "bidirectional"))
      (node (ref "U$4") (pin "P$16") (pinfunction "TXD_P$16") (pintype "bidirectional"))
    )
    (net (code "48") (name "Net-(U$5-2OUT)") (class "Default")
      (node (ref "U$5") (pin "2") (pinfunction "2OUT_2") (pintype "output"))
      (node (ref "U$5") (pin "3") (pinfunction "3OUT_3") (pintype "output"))
    )
    (net (code "49") (name "Net-(U$5-5IN)") (class "Default")
      (node (ref "C2") (pin "2") (pinfunction "2_2") (pintype "passive"))
      (node (ref "C24") (pin "2") (pinfunction "2_2") (pintype "passive"))
      (node (ref "C25") (pin "2") (pinfunction "2_2") (pintype "passive"))
      (node (ref "R10") (pin "1") (pinfunction "1_1") (pintype "passive"))
      (node (ref "R4") (pin "1") (pinfunction "1_1") (pintype "passive"))
      (node (ref "R9") (pin "1") (pinfunction "1_1") (pintype "passive"))
      (node (ref "TSV2") (pin "P$1") (pinfunction "P$1_P$1") (pintype "bidirectional"))
      (node (ref "U$5") (pin "L5") (pinfunction "5IN_L5") (pintype "input"))
    )
    (net (code "50") (name "Net-(U$7-1)") (class "Default")
      (node (ref "C19") (pin "1") (pinfunction "1_1") (pintype "passive"))
      (node (ref "R20") (pin "2") (pinfunction "2_2") (pintype "passive"))
      (node (ref "U$7") (pin "P$1") (pinfunction "1_P$1") (pintype "output"))
    )
    (net (code "51") (name "Net-(U$8-~{1})") (class "Default")
      (node (ref "U$2") (pin "OUT1") (pinfunction "OUT1_OUT1") (pintype "bidirectional"))
      (node (ref "U$8") (pin "~1") (pinfunction "~{1}_~1") (pintype "bidirectional"))
    )
    (net (code "52") (name "Net-(U$8-~{2})") (class "Default")
      (node (ref "U$2") (pin "OUT2") (pinfunction "OUT2_OUT2") (pintype "bidirectional"))
      (node (ref "U$8") (pin "~2") (pinfunction "~{2}_~2") (pintype "bidirectional"))
    )
    (net (code "53") (name "Net-(U$12-BUFIN)") (class "Default")
      (node (ref "U$12") (pin "10") (pinfunction "IOUT_10") (pintype "bidirectional"))
      (node (ref "U$12") (pin "9") (pinfunction "BUFIN_9") (pintype "bidirectional"))
    )
    (net (code "54") (name "Net-(U$12-CAV)") (class "Default")
      (node (ref "C18") (pin "1") (pinfunction "1_1") (pintype "passive"))
      (node (ref "U$12") (pin "6") (pinfunction "CAV_6") (pintype "bidirectional"))
    )
    (net (code "55") (name "Net-(U$12-COM)") (class "Default")
      (node (ref "C13") (pin "1") (pinfunction "1_1") (pintype "passive"))
      (node (ref "R17") (pin "1") (pinfunction "1_1") (pintype "passive"))
      (node (ref "R18") (pin "2") (pinfunction "2_2") (pintype "passive"))
      (node (ref "U$12") (pin "2") (pinfunction "COM_2") (pintype "bidirectional"))
    )
    (net (code "56") (name "Net-(U$12-VIN)") (class "Default")
      (node (ref "C19") (pin "2") (pinfunction "2_2") (pintype "passive"))
      (node (ref "U$12") (pin "4") (pinfunction "VIN_4") (pintype "bidirectional"))
    )
    (net (code "57") (name "Net-(U$13-BUFIN)") (class "Default")
      (node (ref "U$13") (pin "10") (pinfunction "IOUT_10") (pintype "bidirectional"))
      (node (ref "U$13") (pin "9") (pinfunction "BUFIN_9") (pintype "bidirectional"))
    )
    (net (code "58") (name "Net-(U$13-CAV)") (class "Default")
      (node (ref "C12") (pin "1") (pinfunction "1_1") (pintype "passive"))
      (node (ref "U$13") (pin "6") (pinfunction "CAV_6") (pintype "bidirectional"))
    )
    (net (code "59") (name "Net-(U$13-COM)") (class "Default")
      (node (ref "C16") (pin "1") (pinfunction "1_1") (pintype "passive"))
      (node (ref "R3") (pin "1") (pinfunction "1_1") (pintype "passive"))
      (node (ref "R7") (pin "2") (pinfunction "2_2") (pintype "passive"))
      (node (ref "U$13") (pin "2") (pinfunction "COM_2") (pintype "bidirectional"))
    )
    (net (code "60") (name "Net-(U$13-VIN)") (class "Default")
      (node (ref "C11") (pin "2") (pinfunction "2_2") (pintype "passive"))
      (node (ref "U$13") (pin "4") (pinfunction "VIN_4") (pintype "bidirectional"))
    )
    (net (code "61") (name "Net-(U$14-1)") (class "Default")
      (node (ref "C23") (pin "1") (pinfunction "1_1") (pintype "passive"))
      (node (ref "R24") (pin "2") (pinfunction "2_2") (pintype "passive"))
      (node (ref "U$14") (pin "P$1") (pinfunction "1_P$1") (pintype "output"))
    )
    (net (code "62") (name "Net-(U$15-BUFIN)") (class "Default")
      (node (ref "U$15") (pin "10") (pinfunction "IOUT_10") (pintype "bidirectional"))
      (node (ref "U$15") (pin "9") (pinfunction "BUFIN_9") (pintype "bidirectional"))
    )
    (net (code "63") (name "Net-(U$15-CAV)") (class "Default")
      (node (ref "C22") (pin "1") (pinfunction "1_1") (pintype "passive"))
      (node (ref "U$15") (pin "6") (pinfunction "CAV_6") (pintype "bidirectional"))
    )
    (net (code "64") (name "Net-(U$15-COM)") (class "Default")
      (node (ref "C20") (pin "1") (pinfunction "1_1") (pintype "passive"))
      (node (ref "R21") (pin "1") (pinfunction "1_1") (pintype "passive"))
      (node (ref "R22") (pin "2") (pinfunction "2_2") (pintype "passive"))
      (node (ref "U$15") (pin "2") (pinfunction "COM_2") (pintype "bidirectional"))
    )
    (net (code "65") (name "Net-(U$15-VIN)") (class "Default")
      (node (ref "C23") (pin "2") (pinfunction "2_2") (pintype "passive"))
      (node (ref "U$15") (pin "4") (pinfunction "VIN_4") (pintype "bidirectional"))
    )
    (net (code "66") (name "Net-(U$17-~{1})") (class "Default")
      (node (ref "U$16") (pin "OUT1") (pinfunction "OUT1_OUT1") (pintype "bidirectional"))
      (node (ref "U$17") (pin "~1") (pinfunction "~{1}_~1") (pintype "bidirectional"))
    )
    (net (code "67") (name "Net-(U$17-~{2})") (class "Default")
      (node (ref "U$16") (pin "OUT2") (pinfunction "OUT2_OUT2") (pintype "bidirectional"))
      (node (ref "U$17") (pin "~2") (pinfunction "~{2}_~2") (pintype "bidirectional"))
    )
    (net (code "68") (name "Net-(U$19-~{1})") (class "Default")
      (node (ref "U$18") (pin "OUT1") (pinfunction "OUT1_OUT1") (pintype "bidirectional"))
      (node (ref "U$19") (pin "~1") (pinfunction "~{1}_~1") (pintype "bidirectional"))
    )
    (net (code "69") (name "Net-(U$19-~{2})") (class "Default")
      (node (ref "U$18") (pin "OUT2") (pinfunction "OUT2_OUT2") (pintype "bidirectional"))
      (node (ref "U$19") (pin "~2") (pinfunction "~{2}_~2") (pintype "bidirectional"))
    )
    (net (code "70") (name "Net-(X2B-S)") (class "Default")
      (node (ref "R39") (pin "1") (pinfunction "1_1") (pintype "passive"))
      (node (ref "X2") (pin "2") (pinfunction "S_2") (pintype "passive"))
    )
    (net (code "71") (name "Net-(X3B-S)") (class "Default")
      (node (ref "R37") (pin "1") (pinfunction "1_1") (pintype "passive"))
      (node (ref "X3") (pin "2") (pinfunction "S_2") (pintype "passive"))
    )
    (net (code "72") (name "Net-(X4B-S)") (class "Default")
      (node (ref "R38") (pin "1") (pinfunction "1_1") (pintype "passive"))
      (node (ref "X4") (pin "2") (pinfunction "S_2") (pintype "passive"))
    )
    (net (code "73") (name "PE") (class "Default")
      (node (ref "U$20") (pin "PE") (pinfunction "PE_PE") (pintype "input"))
      (node (ref "X1") (pin "P$5") (pinfunction "P$5_P$5") (pintype "bidirectional"))
    )
    (net (code "74") (name "unconnected-(AC1002_1-3-PadP$3)") (class "Default")
      (node (ref "AC1002_1") (pin "P$3") (pinfunction "3_P$3") (pintype "no_connect"))
    )
    (net (code "75") (name "unconnected-(U$1-PadNC)") (class "Default")
      (node (ref "U$1") (pin "NC") (pinfunction "NC_NC") (pintype "bidirectional"))
    )
    (net (code "76") (name "unconnected-(U$1-PadNC1)") (class "Default")
      (node (ref "U$1") (pin "NC1") (pinfunction "NC1_NC1") (pintype "bidirectional"))
    )
    (net (code "77") (name "unconnected-(U$3-CLK-PadSCLOCK)") (class "Default")
      (node (ref "U$3") (pin "SCLOCK") (pinfunction "CLK_SCLOCK") (pintype "bidirectional"))
    )
    (net (code "78") (name "unconnected-(U$3-PadGND2)") (class "Default")
      (node (ref "U$3") (pin "GND2") (pinfunction "GND2_GND2") (pintype "bidirectional"))
    )
    (net (code "79") (name "unconnected-(U$3-PadGND3)") (class "Default")
      (node (ref "U$3") (pin "GND3") (pinfunction "GND3_GND3") (pintype "bidirectional"))
    )
    (net (code "80") (name "unconnected-(U$3-PadMISO)") (class "Default")
      (node (ref "U$3") (pin "MISO") (pinfunction "MISO_MISO") (pintype "bidirectional"))
    )
    (net (code "81") (name "unconnected-(U$3-PadMOSI)") (class "Default")
      (node (ref "U$3") (pin "MOSI") (pinfunction "MOSI_MOSI") (pintype "bidirectional"))
    )
    (net (code "82") (name "unconnected-(U$3-VCC2-PadVCC1)") (class "Default")
      (node (ref "U$3") (pin "VCC1") (pinfunction "VCC2_VCC1") (pintype "bidirectional"))
    )
    (net (code "83") (name "unconnected-(U$4-PadP$1)") (class "Default")
      (node (ref "U$4") (pin "P$1") (pinfunction "P$1_P$1") (pintype "bidirectional"))
    )
    (net (code "84") (name "unconnected-(U$4-PadP$6)") (class "Default")
      (node (ref "U$4") (pin "P$6") (pinfunction "P$6_P$6") (pintype "bidirectional"))
    )
    (net (code "85") (name "unconnected-(U$4-PadP$7)") (class "Default")
      (node (ref "U$4") (pin "P$7") (pinfunction "P$7_P$7") (pintype "bidirectional"))
    )
    (net (code "86") (name "unconnected-(U$4-PadP$8)") (class "Default")
      (node (ref "U$4") (pin "P$8") (pinfunction "P$8_P$8") (pintype "bidirectional"))
    )
    (net (code "87") (name "unconnected-(U$4-PadP$10)") (class "Default")
      (node (ref "U$4") (pin "P$10") (pinfunction "P$10_P$10") (pintype "bidirectional"))
    )
    (net (code "88") (name "unconnected-(U$4-PadP$11)") (class "Default")
      (node (ref "U$4") (pin "P$11") (pinfunction "P$11_P$11") (pintype "bidirectional"))
    )
    (net (code "89") (name "unconnected-(U$4-PadP$12)") (class "Default")
      (node (ref "U$4") (pin "P$12") (pinfunction "P$12_P$12") (pintype "bidirectional"))
    )
    (net (code "90") (name "unconnected-(U$4-PadP$13)") (class "Default")
      (node (ref "U$4") (pin "P$13") (pinfunction "P$13_P$13") (pintype "bidirectional"))
    )
    (net (code "91") (name "unconnected-(U$4-PadP$14)") (class "Default")
      (node (ref "U$4") (pin "P$14") (pinfunction "P$14_P$14") (pintype "bidirectional"))
    )
    (net (code "92") (name "unconnected-(U$4-PadP$15)") (class "Default")
      (node (ref "U$4") (pin "P$15") (pinfunction "P$15_P$15") (pintype "bidirectional"))
    )
    (net (code "93") (name "unconnected-(U$4-PadP$18)") (class "Default")
      (node (ref "U$4") (pin "P$18") (pinfunction "P$18_P$18") (pintype "bidirectional"))
    )
    (net (code "94") (name "unconnected-(U$4-PadP$19)") (class "Default")
      (node (ref "U$4") (pin "P$19") (pinfunction "P$19_P$19") (pintype "bidirectional"))
    )
    (net (code "95") (name "unconnected-(U$4-PadP$22)") (class "Default")
      (node (ref "U$4") (pin "P$22") (pinfunction "P$22_P$22") (pintype "bidirectional"))
    )
    (net (code "96") (name "unconnected-(U$4-PadP$23)") (class "Default")
      (node (ref "U$4") (pin "P$23") (pinfunction "P$23_P$23") (pintype "bidirectional"))
    )
    (net (code "97") (name "unconnected-(U$4-PadP$24)") (class "Default")
      (node (ref "U$4") (pin "P$24") (pinfunction "P$24_P$24") (pintype "bidirectional"))
    )
    (net (code "98") (name "unconnected-(U$4-PadP$26)") (class "Default")
      (node (ref "U$4") (pin "P$26") (pinfunction "P$26_P$26") (pintype "bidirectional"))
    )
    (net (code "99") (name "unconnected-(U$4-PadP$27)") (class "Default")
      (node (ref "U$4") (pin "P$27") (pinfunction "P$27_P$27") (pintype "bidirectional"))
    )
    (net (code "100") (name "unconnected-(U$4-PadP$28)") (class "Default")
      (node (ref "U$4") (pin "P$28") (pinfunction "P$28_P$28") (pintype "bidirectional"))
    )
    (net (code "101") (name "unconnected-(U$4-PadP$29)") (class "Default")
      (node (ref "U$4") (pin "P$29") (pinfunction "P$29_P$29") (pintype "bidirectional"))
    )
    (net (code "102") (name "unconnected-(U$4-PadP$30)") (class "Default")
      (node (ref "U$4") (pin "P$30") (pinfunction "P$30_P$30") (pintype "bidirectional"))
    )
    (net (code "103") (name "unconnected-(U$4-PadP$31)") (class "Default")
      (node (ref "U$4") (pin "P$31") (pinfunction "P$31_P$31") (pintype "bidirectional"))
    )
    (net (code "104") (name "unconnected-(U$7-3-PadP$3)") (class "Default")
      (node (ref "U$7") (pin "P$3") (pinfunction "3_P$3") (pintype "no_connect"))
    )
    (net (code "105") (name "unconnected-(U$12-DB-Pad7)") (class "Default")
      (node (ref "U$12") (pin "7") (pinfunction "DB_7") (pintype "bidirectional"))
    )
    (net (code "106") (name "unconnected-(U$13-DB-Pad7)") (class "Default")
      (node (ref "U$13") (pin "7") (pinfunction "DB_7") (pintype "bidirectional"))
    )
    (net (code "107") (name "unconnected-(U$14-3-PadP$3)") (class "Default")
      (node (ref "U$14") (pin "P$3") (pinfunction "3_P$3") (pintype "no_connect"))
    )
    (net (code "108") (name "unconnected-(U$15-DB-Pad7)") (class "Default")
      (node (ref "U$15") (pin "7") (pinfunction "DB_7") (pintype "bidirectional"))
    )
  )
)
